# 2_AD9833.net
KiCad netlist of a schematic drawn in Altium Designer
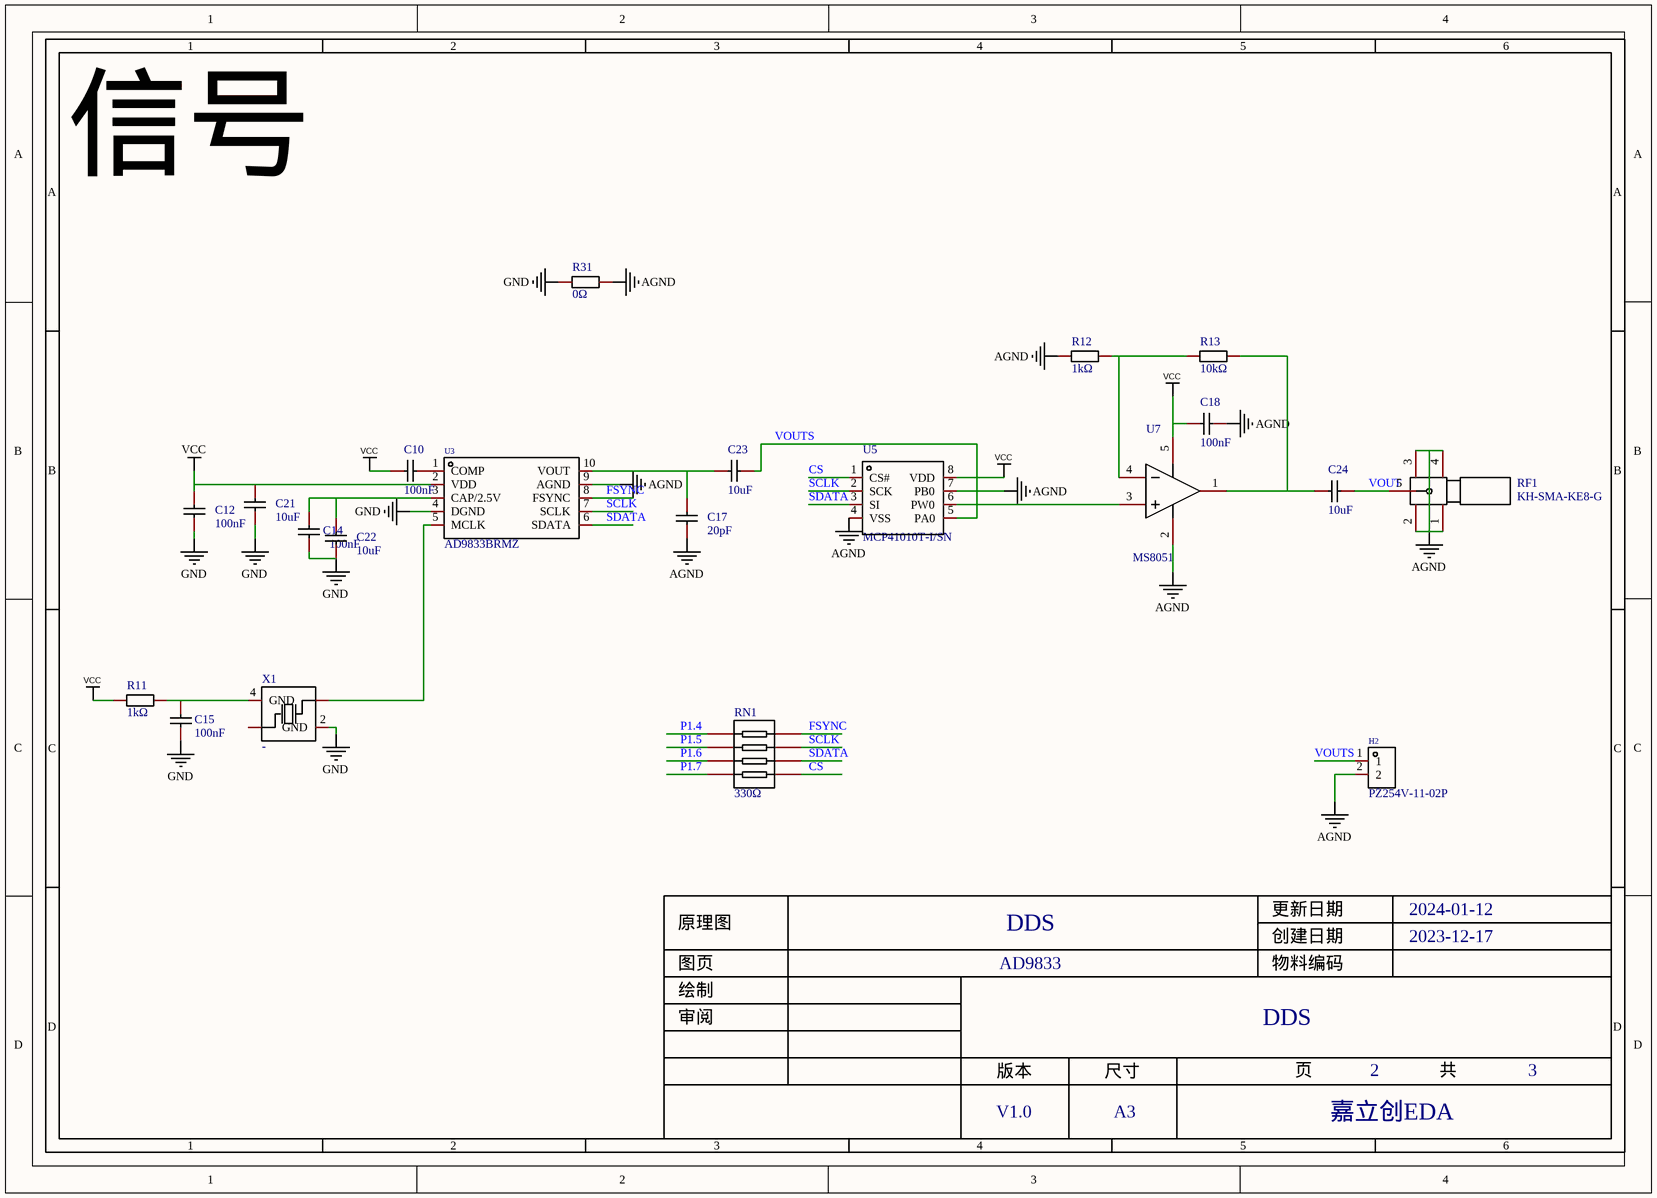
[diagram p0: 2_AD9833.schdoc]

(export (version "E")
  (design (tool "Eeschema 10.0.6"))
  (components
    (comp (ref "C10")
      (value "100nF")
      (description "容值:100nF;精度:±10%;额定电压:50V;材质(温度系数):X7R;")
      (fields
        (field (name "NAME") "100nF")
        (field (name "MANUFACTURER") "FH(风华)")
        (field (name "MANUFACTURER PART") "0805B104K500NT")
      )
      (libsource (lib "altium-import") (part "root_0_0805B104K500NT_"))
    )
    (comp (ref "C12")
      (value "100nF")
      (description "容值:100nF;精度:±10%;额定电压:50V;材质(温度系数):X7R;")
      (fields
        (field (name "NAME") "100nF")
        (field (name "MANUFACTURER") "FH(风华)")
        (field (name "MANUFACTURER PART") "0805B104K500NT")
      )
      (libsource (lib "altium-import") (part "root_1_0805B104K500NT_"))
    )
    (comp (ref "C14")
      (value "100nF")
      (description "容值:100nF;精度:±10%;额定电压:50V;材质(温度系数):X7R;")
      (fields
        (field (name "NAME") "100nF")
        (field (name "MANUFACTURER") "FH(风华)")
        (field (name "MANUFACTURER PART") "0805B104K500NT")
      )
      (libsource (lib "altium-import") (part "root_1_0805B104K500NT_"))
    )
    (comp (ref "C15")
      (value "100nF")
      (description "容值:100nF;精度:±10%;额定电压:50V;材质(温度系数):X7R;")
      (fields
        (field (name "NAME") "100nF")
        (field (name "MANUFACTURER") "FH(风华)")
        (field (name "MANUFACTURER PART") "0805B104K500NT")
      )
      (libsource (lib "altium-import") (part "root_1_0805B104K500NT_"))
    )
    (comp (ref "C17")
      (value "20pF")
      (description "容值:100nF;精度:±10%;额定电压:50V;材质(温度系数):X7R;")
      (fields
        (field (name "NAME") "20pF")
        (field (name "MANUFACTURER") "FH(风华)")
        (field (name "MANUFACTURER PART") "0805B104K500NT")
      )
      (libsource (lib "altium-import") (part "root_1_0805B104K500NT_"))
    )
    (comp (ref "C18")
      (value "100nF")
      (description "容值:100nF;精度:±10%;额定电压:50V;材质(温度系数):X7R;")
      (fields
        (field (name "NAME") "100nF")
        (field (name "MANUFACTURER") "FH(风华)")
        (field (name "MANUFACTURER PART") "0805B104K500NT")
      )
      (libsource (lib "altium-import") (part "root_0_0805B104K500NT_"))
    )
    (comp (ref "C21")
      (value "10uF")
      (description "容值:10uF;精度:±10%;额定电压:50V;材质(温度系数):X5R;")
      (fields
        (field (name "NAME") "10uF")
        (field (name "MANUFACTURER") "SAMSUNG(三星)")
        (field (name "MANUFACTURER PART") "CL31A106KBHNNNE")
      )
      (libsource (lib "altium-import") (part "root_1_CL31A106KBHNNNE_"))
    )
    (comp (ref "C22")
      (value "10uF")
      (description "容值:10uF;精度:±10%;额定电压:50V;材质(温度系数):X5R;")
      (fields
        (field (name "NAME") "10uF")
        (field (name "MANUFACTURER") "SAMSUNG(三星)")
        (field (name "MANUFACTURER PART") "CL31A106KBHNNNE")
      )
      (libsource (lib "altium-import") (part "root_1_CL31A106KBHNNNE_"))
    )
    (comp (ref "C23")
      (value "10uF")
      (description "容值:10uF;精度:±10%;额定电压:50V;材质(温度系数):X5R;")
      (fields
        (field (name "NAME") "10uF")
        (field (name "MANUFACTURER") "SAMSUNG(三星)")
        (field (name "MANUFACTURER PART") "CL31A106KBHNNNE")
      )
      (libsource (lib "altium-import") (part "root_0_CL31A106KBHNNNE_"))
    )
    (comp (ref "C24")
      (value "10uF")
      (description "容值:10uF;精度:±10%;额定电压:50V;材质(温度系数):X5R;")
      (fields
        (field (name "NAME") "10uF")
        (field (name "MANUFACTURER") "SAMSUNG(三星)")
        (field (name "MANUFACTURER PART") "CL31A106KBHNNNE")
      )
      (libsource (lib "altium-import") (part "root_0_CL31A106KBHNNNE_"))
    )
    (comp (ref "H2")
      (value "PZ254V-11-02P")
      (fields (field (name "NAME") "PZ254V-11-02P") (field (name "MANUFACTURER") "XFCN(兴飞)"))
      (libsource (lib "altium-import") (part "root_0_PZ254V-11-02P_"))
    )
    (comp (ref "R11")
      (value "1kΩ")
      (description "阻值:1kΩ;精度:±1%;功率:125mW;温度系数:±100ppm/℃;电阻类型:厚膜电阻;")
      (fields
        (field (name "NAME") "1kΩ")
        (field (name "MANUFACTURER") "UNI-ROYAL(厚声)")
        (field (name "MANUFACTURER PART") "0805W8F1001T5E")
      )
      (libsource (lib "altium-import") (part "root_0_0805W8F1001T5E_"))
    )
    (comp (ref "R12")
      (value "1kΩ")
      (description "阻值:1kΩ;精度:±1%;功率:125mW;温度系数:±100ppm/℃;电阻类型:厚膜电阻;")
      (fields
        (field (name "NAME") "1kΩ")
        (field (name "MANUFACTURER") "UNI-ROYAL(厚声)")
        (field (name "MANUFACTURER PART") "0805W8F1001T5E")
      )
      (libsource (lib "altium-import") (part "root_0_0805W8F1001T5E_"))
    )
    (comp (ref "R13")
      (value "10kΩ")
      (description "阻值:1kΩ;精度:±1%;功率:125mW;温度系数:±100ppm/℃;电阻类型:厚膜电阻;")
      (fields
        (field (name "NAME") "10kΩ")
        (field (name "MANUFACTURER") "UNI-ROYAL(厚声)")
        (field (name "MANUFACTURER PART") "0805W8F1001T5E")
      )
      (libsource (lib "altium-import") (part "root_0_0805W8F1001T5E_"))
    )
    (comp (ref "R31")
      (value "0Ω")
      (description "电阻类型:厚膜电阻;阻值:0Ω;精度:±1%;功率:125mW;")
      (fields
        (field (name "NAME") "0Ω")
        (field (name "MANUFACTURER") "UNI-ROYAL(厚声)")
        (field (name "MANUFACTURER PART") "0805W8F0000T5E")
      )
      (libsource (lib "altium-import") (part "root_0_0805W8F0000T5E_"))
    )
    (comp (ref "RF1")
      (value "KH-SMA-KE8-G")
      (description "连接器类型:板端;接口类型:内孔;频率-最大值:-;接口直径:-;射频系列:SMA;端口数量:1;阻抗:-;样式:偏脚;接口长度/高度:8mm;工作温度范围:-;")
      (fields (field (name "NAME") "KH-SMA-KE8-G") (field (name "MANUFACTURER") "kinghelm(金航标)"))
      (libsource (lib "altium-import") (part "root_2_KH-SMA-KE8-G_"))
    )
    (comp (ref "RN1")
      (value "330Ω")
      (description "阻值:330Ω;精度:±5%;单个元件功率:62.5mW;电阻器数:4;温度系数:±200ppm/℃;")
      (fields
        (field (name "NAME") "330Ω")
        (field (name "MANUFACTURER") "UNI-ROYAL(厚声)")
        (field (name "MANUFACTURER PART") "4D03WGJ0331T5E")
      )
      (libsource (lib "altium-import") (part "root_0_4D03WGJ0331T5E_"))
    )
    (comp (ref "U3")
      (value "AD9833BRMZ")
      (description "电源电压:2.3V~5.5V;分辨率(位):10;自宽调谐(最大值):28b;")
      (fields (field (name "NAME") "AD9833BRMZ") (field (name "MANUFACTURER") "ADI(亚德诺)"))
      (libsource (lib "altium-import") (part "root_0_AD9833BRMZ_"))
    )
    (comp (ref "U5")
      (value "MCP41010T-I/SN")
      (description "供电电压:2.7V~5.5V;电阻值(欧姆):10kΩ;精度:±20%;接口类型:SPI;")
      (fields (field (name "NAME") "MCP41010T-I/SN") (field (name "MANUFACTURER") "MICROCHIP(美国微芯)"))
      (libsource (lib "altium-import") (part "root_0_MCP41010T-I/SN_"))
    )
    (comp (ref "U7")
      (value "MS8051")
      (description "运放类型:-;放大器组数:-;增益带宽积（GBP）:-;压摆率（SR）:-;电源电压:-;各通道供电电流:-;")
      (fields (field (name "NAME") "MS8051") (field (name "MANUFACTURER") "Corebai(芯佰微)"))
      (libsource (lib "altium-import") (part "root_0_CBM8051AST5_"))
    )
    (comp (ref "X1")
      (value "-")
      (description "频率:-;负载电容:-;")
      (fields
        (field (name "NAME") "-")
        (field (name "MANUFACTURER") "TKD(泰晶)")
        (field (name "MANUFACTURER PART") "SX32Y025000BK1T")
      )
      (libsource (lib "altium-import") (part "root_0_SX32Y025000BK1T_"))
    )
  )
  (nets
    (net (code "1") (name "/CS") (class "Default")
      (node (ref "RN1") (pin "5") (pinfunction "5_5") (pintype "passive"))
      (node (ref "U5") (pin "1") (pinfunction "CS#_1") (pintype "passive"))
    )
    (net (code "2") (name "/FSYNC") (class "Default")
      (node (ref "RN1") (pin "8") (pinfunction "8_8") (pintype "passive"))
      (node (ref "U3") (pin "8") (pinfunction "FSYNC_8") (pintype "passive"))
    )
    (net (code "3") (name "/P1.4") (class "Default")
      (node (ref "RN1") (pin "1") (pinfunction "1_1") (pintype "passive"))
    )
    (net (code "4") (name "/P1.5") (class "Default")
      (node (ref "RN1") (pin "2") (pinfunction "2_2") (pintype "passive"))
    )
    (net (code "5") (name "/P1.6") (class "Default")
      (node (ref "RN1") (pin "3") (pinfunction "3_3") (pintype "passive"))
    )
    (net (code "6") (name "/P1.7") (class "Default")
      (node (ref "RN1") (pin "4") (pinfunction "4_4") (pintype "passive"))
    )
    (net (code "7") (name "/SCLK") (class "Default")
      (node (ref "RN1") (pin "7") (pinfunction "7_7") (pintype "passive"))
      (node (ref "U3") (pin "7") (pinfunction "SCLK_7") (pintype "passive"))
      (node (ref "U5") (pin "2") (pinfunction "SCK_2") (pintype "passive"))
    )
    (net (code "8") (name "/SDATA") (class "Default")
      (node (ref "RN1") (pin "6") (pinfunction "6_6") (pintype "passive"))
      (node (ref "U3") (pin "6") (pinfunction "SDATA_6") (pintype "passive"))
      (node (ref "U5") (pin "3") (pinfunction "SI_3") (pintype "passive"))
    )
    (net (code "9") (name "/VOUT") (class "Default")
      (node (ref "C24") (pin "2") (pinfunction "2_2") (pintype "passive"))
      (node (ref "RF1") (pin "5") (pinfunction "5_5") (pintype "passive"))
    )
    (net (code "10") (name "/VOUTS") (class "Default")
      (node (ref "C23") (pin "2") (pinfunction "2_2") (pintype "passive"))
      (node (ref "H2") (pin "1") (pinfunction "1_1") (pintype "passive"))
      (node (ref "U5") (pin "5") (pinfunction "PA0_5") (pintype "passive"))
    )
    (net (code "11") (name "AGND") (class "Default")
      (node (ref "C17") (pin "1") (pinfunction "1_1") (pintype "passive"))
      (node (ref "C18") (pin "2") (pinfunction "2_2") (pintype "passive"))
      (node (ref "H2") (pin "2") (pinfunction "2_2") (pintype "passive"))
      (node (ref "R12") (pin "1") (pinfunction "1_1") (pintype "passive"))
      (node (ref "R31") (pin "2") (pinfunction "2_2") (pintype "passive"))
      (node (ref "RF1") (pin "1") (pinfunction "1_1") (pintype "passive"))
      (node (ref "RF1") (pin "2") (pinfunction "2_2") (pintype "passive"))
      (node (ref "RF1") (pin "3") (pinfunction "3_3") (pintype "passive"))
      (node (ref "RF1") (pin "4") (pinfunction "4_4") (pintype "passive"))
      (node (ref "U3") (pin "9") (pinfunction "AGND_9") (pintype "passive"))
      (node (ref "U5") (pin "4") (pinfunction "VSS_4") (pintype "passive"))
      (node (ref "U5") (pin "7") (pinfunction "PB0_7") (pintype "passive"))
      (node (ref "U7") (pin "2") (pinfunction "VSS_2") (pintype "passive"))
    )
    (net (code "12") (name "GND") (class "Default")
      (node (ref "C12") (pin "1") (pinfunction "1_1") (pintype "passive"))
      (node (ref "C14") (pin "1") (pinfunction "1_1") (pintype "passive"))
      (node (ref "C15") (pin "1") (pinfunction "1_1") (pintype "passive"))
      (node (ref "C21") (pin "1") (pinfunction "1_1") (pintype "passive"))
      (node (ref "C22") (pin "1") (pinfunction "1_1") (pintype "passive"))
      (node (ref "R31") (pin "1") (pinfunction "1_1") (pintype "passive"))
      (node (ref "U3") (pin "4") (pinfunction "DGND_4") (pintype "passive"))
      (node (ref "X1") (pin "2") (pinfunction "GND_2") (pintype "passive"))
    )
    (net (code "13") (name "Net-(C15-Pad2)") (class "Default")
      (node (ref "C15") (pin "2") (pinfunction "2_2") (pintype "passive"))
      (node (ref "R11") (pin "2") (pinfunction "2_2") (pintype "passive"))
      (node (ref "X1") (pin "4") (pinfunction "GND_4") (pintype "passive"))
    )
    (net (code "14") (name "Net-(U3-CAP{slash}2.5V)") (class "Default")
      (node (ref "C14") (pin "2") (pinfunction "2_2") (pintype "passive"))
      (node (ref "C22") (pin "2") (pinfunction "2_2") (pintype "passive"))
      (node (ref "U3") (pin "3") (pinfunction "CAP/2.5V_3") (pintype "passive"))
    )
    (net (code "15") (name "Net-(U3-COMP)") (class "Default")
      (node (ref "C10") (pin "2") (pinfunction "2_2") (pintype "passive"))
      (node (ref "U3") (pin "1") (pinfunction "COMP_1") (pintype "passive"))
    )
    (net (code "16") (name "Net-(U3-MCLK)") (class "Default")
      (node (ref "U3") (pin "5") (pinfunction "MCLK_5") (pintype "passive"))
      (node (ref "X1") (pin "3") (pinfunction "OSC2_3") (pintype "passive"))
    )
    (net (code "17") (name "Net-(U3-VOUT)") (class "Default")
      (node (ref "C17") (pin "2") (pinfunction "2_2") (pintype "passive"))
      (node (ref "C23") (pin "1") (pinfunction "1_1") (pintype "passive"))
      (node (ref "U3") (pin "10") (pinfunction "VOUT_10") (pintype "passive"))
    )
    (net (code "18") (name "Net-(U5-PW0)") (class "Default")
      (node (ref "U5") (pin "6") (pinfunction "PW0_6") (pintype "passive"))
      (node (ref "U7") (pin "3") (pinfunction "IN+_3") (pintype "passive"))
    )
    (net (code "19") (name "Net-(U7-IN-)") (class "Default")
      (node (ref "R12") (pin "2") (pinfunction "2_2") (pintype "passive"))
      (node (ref "R13") (pin "1") (pinfunction "1_1") (pintype "passive"))
      (node (ref "U7") (pin "4") (pinfunction "IN-_4") (pintype "passive"))
    )
    (net (code "20") (name "Net-(U7-OUT)") (class "Default")
      (node (ref "C24") (pin "1") (pinfunction "1_1") (pintype "passive"))
      (node (ref "R13") (pin "2") (pinfunction "2_2") (pintype "passive"))
      (node (ref "U7") (pin "1") (pinfunction "OUT_1") (pintype "passive"))
    )
    (net (code "21") (name "VCC") (class "Default")
      (node (ref "C10") (pin "1") (pinfunction "1_1") (pintype "passive"))
      (node (ref "C12") (pin "2") (pinfunction "2_2") (pintype "passive"))
      (node (ref "C18") (pin "1") (pinfunction "1_1") (pintype "passive"))
      (node (ref "C21") (pin "2") (pinfunction "2_2") (pintype "passive"))
      (node (ref "R11") (pin "1") (pinfunction "1_1") (pintype "passive"))
      (node (ref "U3") (pin "2") (pinfunction "VDD_2") (pintype "passive"))
      (node (ref "U5") (pin "8") (pinfunction "VDD_8") (pintype "passive"))
      (node (ref "U7") (pin "5") (pinfunction "VDD_5") (pintype "passive"))
    )
    (net (code "22") (name "unconnected-(X1-OSC1-Pad1)") (class "Default")
      (node (ref "X1") (pin "1") (pinfunction "OSC1_1") (pintype "passive"))
    )
  )
)
